# Sheet1.net
KiCad netlist of a schematic drawn in Altium Designer
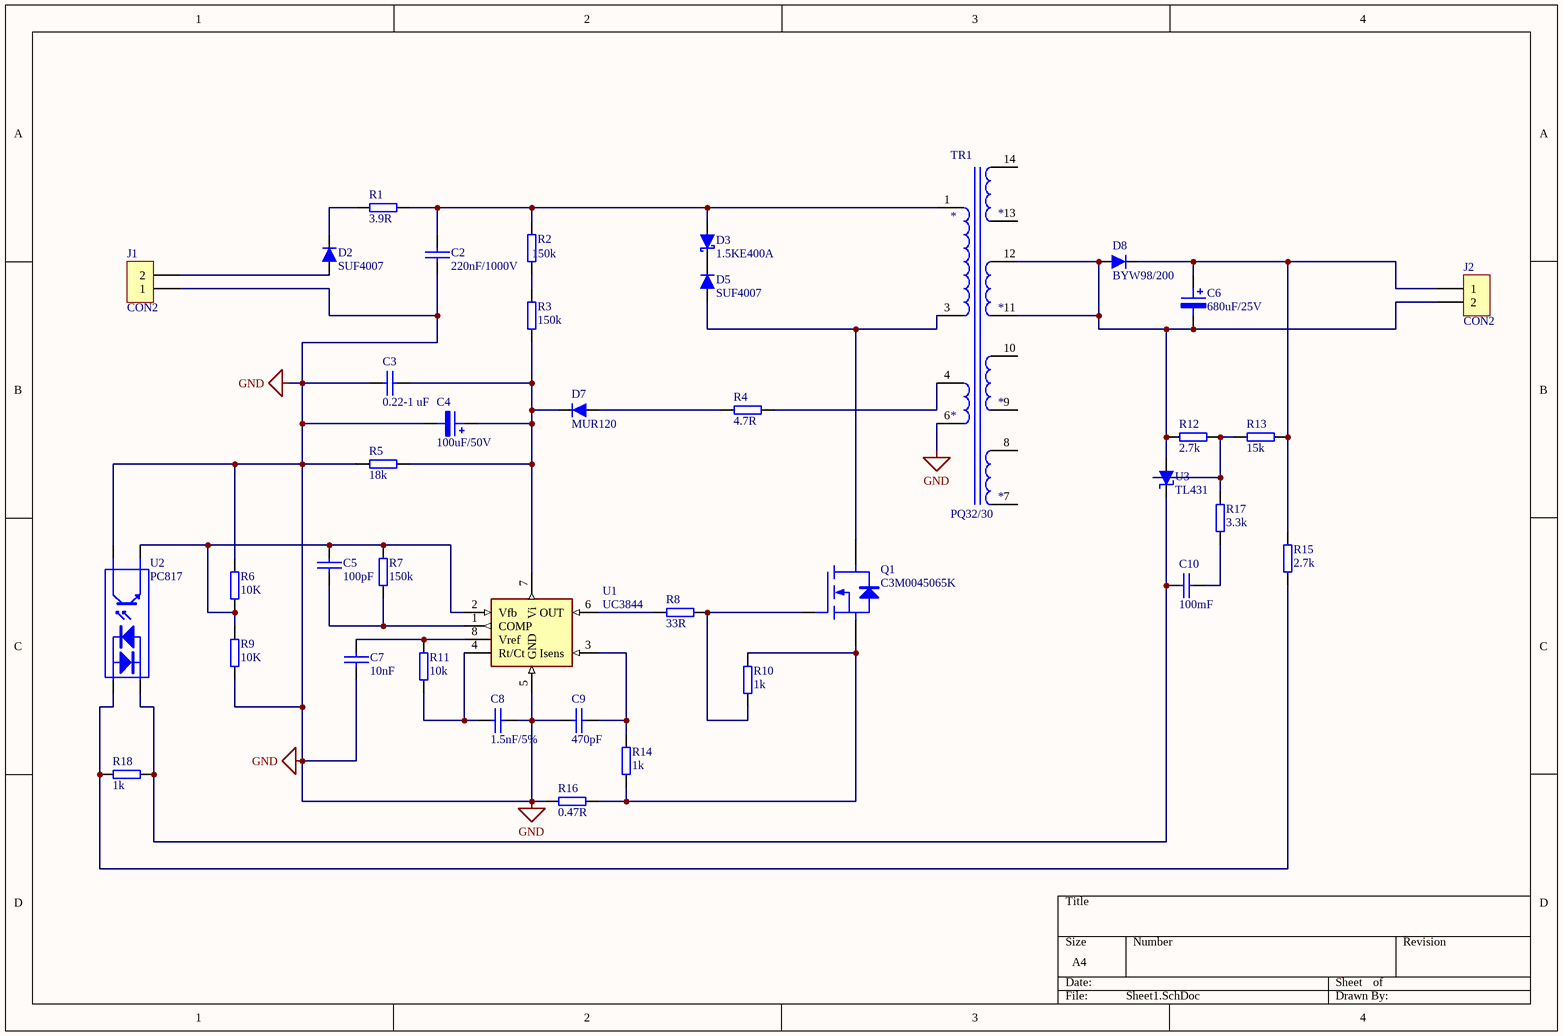
[diagram p0: Sheet1.SchDoc]

(export (version "E")
  (design (tool "Eeschema 10.0.6"))
  (components
    (comp (ref "C2")
      (value "220nF/1000V")
      (footprint "MKP_R22,5_26,5x10,5")
      (description "Capacitor")
      (libsource (lib "alt_sch") (part "C"))
    )
    (comp (ref "C3")
      (value "0.22-1 uF")
      (footprint "1206_O")
      (description "Capacitor")
      (libsource (lib "alt_sch") (part "C"))
    )
    (comp (ref "C4")
      (value "100uF/50V")
      (footprint "AL04/10")
      (description "Electrolytic Capacitor")
      (libsource (lib "alt_sch") (part "C-EL"))
    )
    (comp (ref "C5")
      (value "100pF")
      (footprint "1206_O")
      (description "Capacitor")
      (libsource (lib "alt_sch") (part "C"))
    )
    (comp (ref "C6")
      (value "680uF/25V")
      (footprint "AL04/18")
      (description "Electrolytic Capacitor")
      (libsource (lib "alt_sch") (part "C-EL"))
    )
    (comp (ref "C7")
      (value "10nF")
      (footprint "1206_O")
      (description "Capacitor")
      (libsource (lib "alt_sch") (part "C"))
    )
    (comp (ref "C8")
      (value "1.5nF/5%")
      (footprint "1206_O")
      (description "Capacitor")
      (libsource (lib "alt_sch") (part "C"))
    )
    (comp (ref "C9")
      (value "470pF")
      (footprint "1206_O")
      (description "Capacitor")
      (libsource (lib "alt_sch") (part "C"))
    )
    (comp (ref "C10")
      (value "100mF")
      (footprint "1206_O")
      (description "Capacitor")
      (libsource (lib "alt_sch") (part "C"))
    )
    (comp (ref "D2") (value "SUF4007") (footprint "DO-35") (libsource (lib "alt_sch") (part "DIODE")))
    (comp (ref "D3")
      (value "1.5KE400A")
      (footprint "DO-35")
      (libsource (lib "alt_sch") (part "DIODE_SCHOTTKY"))
    )
    (comp (ref "D5") (value "SUF4007") (footprint "DO-35") (libsource (lib "alt_sch") (part "DIODE")))
    (comp (ref "D7") (value "MUR120") (footprint "1206_D") (libsource (lib "alt_sch") (part "DIODE")))
    (comp (ref "D8") (value "BYW98/200") (footprint "DO-35") (libsource (lib "alt_sch") (part "DIODE")))
    (comp (ref "J1")
      (value "CON2")
      (footprint "MSTB/2A")
      (description "Connector")
      (libsource (lib "Mis-Ep") (part "CON2"))
    )
    (comp (ref "J2")
      (value "CON2")
      (footprint "MSTB/2A")
      (description "Connector")
      (libsource (lib "") (part "CON2_1"))
    )
    (comp (ref "Q1")
      (value "C3M0045065K")
      (footprint "TO-247AC_V")
      (description "MOSFET")
      (libsource (lib "alt_sch") (part "MOSFET"))
    )
    (comp (ref "R1") (value "3.9R") (footprint "MLT2") (libsource (lib "alt_sch") (part "R")))
    (comp (ref "R2") (value "150k") (footprint "MLT2") (libsource (lib "alt_sch") (part "R")))
    (comp (ref "R3") (value "150k") (footprint "MLT2") (libsource (lib "alt_sch") (part "R")))
    (comp (ref "R4") (value "4.7R") (footprint "1206_O") (libsource (lib "alt_sch") (part "R")))
    (comp (ref "R5") (value "18k") (footprint "1206_O") (libsource (lib "alt_sch") (part "R")))
    (comp (ref "R6") (value "10K") (footprint "1206_O") (libsource (lib "alt_sch") (part "R")))
    (comp (ref "R7") (value "150k") (footprint "1206_O") (libsource (lib "alt_sch") (part "R")))
    (comp (ref "R8") (value "33R") (footprint "1206_O") (libsource (lib "alt_sch") (part "R")))
    (comp (ref "R9") (value "10K") (footprint "1206_O") (libsource (lib "alt_sch") (part "R")))
    (comp (ref "R10") (value "1k") (footprint "1206_O") (libsource (lib "alt_sch") (part "R")))
    (comp (ref "R11") (value "10k") (footprint "1206_O") (libsource (lib "alt_sch") (part "R")))
    (comp (ref "R12") (value "2.7k") (footprint "1206_O") (libsource (lib "alt_sch") (part "R")))
    (comp (ref "R13") (value "15k") (footprint "1206_O") (libsource (lib "alt_sch") (part "R")))
    (comp (ref "R14") (value "1k") (footprint "1206_O") (libsource (lib "alt_sch") (part "R")))
    (comp (ref "R15") (value "2.7k") (footprint "1206_O") (libsource (lib "alt_sch") (part "R")))
    (comp (ref "R16") (value "0.47R") (footprint "1206_O") (libsource (lib "alt_sch") (part "R")))
    (comp (ref "R17") (value "3.3k") (footprint "1206_O") (libsource (lib "alt_sch") (part "R")))
    (comp (ref "R18") (value "1k") (footprint "1206_O") (libsource (lib "alt_sch") (part "R")))
    (comp (ref "TR1") (value "PQ32/30") (footprint "ETD39") (libsource (lib "Mis-Ep") (part "TRANS9")))
    (comp (ref "U1") (value "UC3844") (footprint "DIP8") (libsource (lib "alt_sch") (part "UC3844")))
    (comp (ref "U2")
      (value "PC817")
      (footprint "DIP4")
      (description "Optoisolator")
      (libsource (lib "alt_sch") (part "OPTOISO1"))
    )
    (comp (ref "U3") (value "TL431") (footprint "SOT23") (libsource (lib "alt_sch") (part "VREF_SOT23")))
  )
  (nets
    (net (code "1") (name "GND") (class "Default")
      (node (ref "C2") (pin "2") (pinfunction "2_2") (pintype "passive"))
      (node (ref "C3") (pin "1") (pinfunction "1_1") (pintype "passive"))
      (node (ref "C4") (pin "2") (pinfunction "2_2") (pintype "passive"))
      (node (ref "C7") (pin "1") (pinfunction "1_1") (pintype "passive"))
      (node (ref "C8") (pin "2") (pinfunction "2_2") (pintype "passive"))
      (node (ref "C9") (pin "1") (pinfunction "1_1") (pintype "passive"))
      (node (ref "J1") (pin "1") (pinfunction "1_1") (pintype "passive"))
      (node (ref "R16") (pin "1") (pinfunction "1_1") (pintype "passive"))
      (node (ref "R5") (pin "2") (pinfunction "2_2") (pintype "passive"))
      (node (ref "R6") (pin "1") (pinfunction "1_1") (pintype "passive"))
      (node (ref "R9") (pin "2") (pinfunction "2_2") (pintype "passive"))
      (node (ref "TR1") (pin "6") (pinfunction "6_6") (pintype "passive"))
      (node (ref "U1") (pin "5") (pinfunction "GND_5") (pintype "input"))
      (node (ref "U2") (pin "4") (pinfunction "4_4") (pintype "passive"))
    )
    (net (code "2") (name "Net-(C2-Pad1)") (class "Default")
      (node (ref "C2") (pin "1") (pinfunction "1_1") (pintype "passive"))
      (node (ref "D3") (pin "A") (pinfunction "A_A") (pintype "passive"))
      (node (ref "R1") (pin "1") (pinfunction "1_1") (pintype "passive"))
      (node (ref "R2") (pin "2") (pinfunction "2_2") (pintype "passive"))
      (node (ref "TR1") (pin "1") (pinfunction "1_1") (pintype "passive"))
    )
    (net (code "3") (name "Net-(C6-Pad1)") (class "Default")
      (node (ref "C6") (pin "1") (pinfunction "1_1") (pintype "passive"))
      (node (ref "D8") (pin "K") (pinfunction "K_K") (pintype "passive"))
      (node (ref "J2") (pin "1") (pinfunction "1_1") (pintype "passive"))
      (node (ref "R13") (pin "1") (pinfunction "1_1") (pintype "passive"))
      (node (ref "R15") (pin "1") (pinfunction "1_1") (pintype "passive"))
    )
    (net (code "4") (name "Net-(C6-Pad2)") (class "Default")
      (node (ref "C6") (pin "2") (pinfunction "2_2") (pintype "passive"))
      (node (ref "D8") (pin "A") (pinfunction "A_A") (pintype "passive"))
      (node (ref "J2") (pin "2") (pinfunction "2_2") (pintype "passive"))
      (node (ref "R12") (pin "1") (pinfunction "1_1") (pintype "passive"))
      (node (ref "TR1") (pin "11") (pinfunction "11_11") (pintype "passive"))
      (node (ref "TR1") (pin "12") (pinfunction "12_12") (pintype "passive"))
      (node (ref "U3") (pin "C") (pinfunction "C_C") (pintype "passive"))
    )
    (net (code "5") (name "Net-(C10-Pad1)") (class "Default")
      (node (ref "C10") (pin "1") (pinfunction "1_1") (pintype "passive"))
      (node (ref "R18") (pin "1") (pinfunction "1_1") (pintype "passive"))
      (node (ref "U2") (pin "2") (pinfunction "2_2") (pintype "passive"))
      (node (ref "U3") (pin "B") (pinfunction "B_B") (pintype "passive"))
    )
    (net (code "6") (name "Net-(C10-Pad2)") (class "Default")
      (node (ref "C10") (pin "2") (pinfunction "2_2") (pintype "passive"))
      (node (ref "R17") (pin "2") (pinfunction "2_2") (pintype "passive"))
    )
    (net (code "7") (name "Net-(D2-PadA)") (class "Default")
      (node (ref "D2") (pin "A") (pinfunction "A_A") (pintype "passive"))
      (node (ref "J1") (pin "2") (pinfunction "2_2") (pintype "passive"))
    )
    (net (code "8") (name "Net-(D2-PadK)") (class "Default")
      (node (ref "D2") (pin "K") (pinfunction "K_K") (pintype "passive"))
      (node (ref "R1") (pin "2") (pinfunction "2_2") (pintype "passive"))
    )
    (net (code "9") (name "Net-(D3-PadK)") (class "Default")
      (node (ref "D3") (pin "K") (pinfunction "K_K") (pintype "passive"))
      (node (ref "D5") (pin "K") (pinfunction "K_K") (pintype "passive"))
    )
    (net (code "10") (name "Net-(D5-PadA)") (class "Default")
      (node (ref "D5") (pin "A") (pinfunction "A_A") (pintype "passive"))
      (node (ref "Q1") (pin "C") (pinfunction "C_C") (pintype "passive"))
      (node (ref "TR1") (pin "3") (pinfunction "3_3") (pintype "passive"))
    )
    (net (code "11") (name "Net-(D7-PadA)") (class "Default")
      (node (ref "D7") (pin "A") (pinfunction "A_A") (pintype "passive"))
      (node (ref "R4") (pin "1") (pinfunction "1_1") (pintype "passive"))
    )
    (net (code "12") (name "Net-(Q1-PadB)") (class "Default")
      (node (ref "Q1") (pin "B") (pinfunction "B_B") (pintype "passive"))
      (node (ref "R10") (pin "2") (pinfunction "2_2") (pintype "passive"))
      (node (ref "R8") (pin "2") (pinfunction "2_2") (pintype "passive"))
    )
    (net (code "13") (name "Net-(Q1-PadE)") (class "Default")
      (node (ref "Q1") (pin "E") (pinfunction "E_E") (pintype "passive"))
      (node (ref "R10") (pin "1") (pinfunction "1_1") (pintype "passive"))
      (node (ref "R14") (pin "2") (pinfunction "2_2") (pintype "passive"))
      (node (ref "R16") (pin "2") (pinfunction "2_2") (pintype "passive"))
    )
    (net (code "14") (name "Net-(R2-Pad1)") (class "Default")
      (node (ref "R2") (pin "1") (pinfunction "1_1") (pintype "passive"))
      (node (ref "R3") (pin "2") (pinfunction "2_2") (pintype "passive"))
    )
    (net (code "15") (name "Net-(R4-Pad2)") (class "Default")
      (node (ref "R4") (pin "2") (pinfunction "2_2") (pintype "passive"))
      (node (ref "TR1") (pin "4") (pinfunction "4_4") (pintype "passive"))
    )
    (net (code "16") (name "Net-(R12-Pad2)") (class "Default")
      (node (ref "R12") (pin "2") (pinfunction "2_2") (pintype "passive"))
      (node (ref "R13") (pin "2") (pinfunction "2_2") (pintype "passive"))
      (node (ref "R17") (pin "1") (pinfunction "1_1") (pintype "passive"))
      (node (ref "U3") (pin "E") (pinfunction "E_E") (pintype "passive"))
    )
    (net (code "17") (name "Net-(R15-Pad2)") (class "Default")
      (node (ref "R15") (pin "2") (pinfunction "2_2") (pintype "passive"))
      (node (ref "R18") (pin "2") (pinfunction "2_2") (pintype "passive"))
      (node (ref "U2") (pin "1") (pinfunction "1_1") (pintype "passive"))
    )
    (net (code "18") (name "Net-(U1-COMP)") (class "Default")
      (node (ref "C5") (pin "1") (pinfunction "1_1") (pintype "passive"))
      (node (ref "R7") (pin "2") (pinfunction "2_2") (pintype "passive"))
      (node (ref "U1") (pin "1") (pinfunction "COMP_1") (pintype "output"))
    )
    (net (code "19") (name "Net-(U1-Isens)") (class "Default")
      (node (ref "C9") (pin "2") (pinfunction "2_2") (pintype "passive"))
      (node (ref "R14") (pin "1") (pinfunction "1_1") (pintype "passive"))
      (node (ref "U1") (pin "3") (pinfunction "Isens_3") (pintype "input"))
    )
    (net (code "20") (name "Net-(U1-OUT)") (class "Default")
      (node (ref "R8") (pin "1") (pinfunction "1_1") (pintype "passive"))
      (node (ref "U1") (pin "6") (pinfunction "OUT_6") (pintype "input"))
    )
    (net (code "21") (name "Net-(U1-Rt{slash}Ct)") (class "Default")
      (node (ref "C8") (pin "1") (pinfunction "1_1") (pintype "passive"))
      (node (ref "R11") (pin "2") (pinfunction "2_2") (pintype "passive"))
      (node (ref "U1") (pin "4") (pinfunction "Rt/Ct_4") (pintype "power_in"))
    )
    (net (code "22") (name "Net-(U1-Vfb)") (class "Default")
      (node (ref "C5") (pin "2") (pinfunction "2_2") (pintype "passive"))
      (node (ref "R6") (pin "2") (pinfunction "2_2") (pintype "passive"))
      (node (ref "R7") (pin "1") (pinfunction "1_1") (pintype "passive"))
      (node (ref "R9") (pin "1") (pinfunction "1_1") (pintype "passive"))
      (node (ref "U1") (pin "2") (pinfunction "Vfb_2") (pintype "input"))
      (node (ref "U2") (pin "3") (pinfunction "3_3") (pintype "passive"))
    )
    (net (code "23") (name "Net-(U1-Vi)") (class "Default")
      (node (ref "C3") (pin "2") (pinfunction "2_2") (pintype "passive"))
      (node (ref "C4") (pin "1") (pinfunction "1_1") (pintype "passive"))
      (node (ref "D7") (pin "K") (pinfunction "K_K") (pintype "passive"))
      (node (ref "R3") (pin "1") (pinfunction "1_1") (pintype "passive"))
      (node (ref "R5") (pin "1") (pinfunction "1_1") (pintype "passive"))
      (node (ref "U1") (pin "7") (pinfunction "Vi_7") (pintype "output"))
    )
    (net (code "24") (name "Net-(U1-Vref)") (class "Default")
      (node (ref "C7") (pin "2") (pinfunction "2_2") (pintype "passive"))
      (node (ref "R11") (pin "1") (pinfunction "1_1") (pintype "passive"))
      (node (ref "U1") (pin "8") (pinfunction "Vref_8") (pintype "power_in"))
    )
    (net (code "25") (name "unconnected-(TR1-Pad7)") (class "Default")
      (node (ref "TR1") (pin "7") (pinfunction "7_7") (pintype "passive"))
    )
    (net (code "26") (name "unconnected-(TR1-Pad8)") (class "Default")
      (node (ref "TR1") (pin "8") (pinfunction "8_8") (pintype "passive"))
    )
    (net (code "27") (name "unconnected-(TR1-Pad9)") (class "Default")
      (node (ref "TR1") (pin "9") (pinfunction "9_9") (pintype "passive"))
    )
    (net (code "28") (name "unconnected-(TR1-Pad10)") (class "Default")
      (node (ref "TR1") (pin "10") (pinfunction "10_10") (pintype "passive"))
    )
    (net (code "29") (name "unconnected-(TR1-Pad13)") (class "Default")
      (node (ref "TR1") (pin "13") (pinfunction "13_13") (pintype "passive"))
    )
    (net (code "30") (name "unconnected-(TR1-Pad14)") (class "Default")
      (node (ref "TR1") (pin "14") (pinfunction "14_14") (pintype "passive"))
    )
  )
)
